# INF_Processing.net
KiCad netlist of a schematic drawn in Altium Designer
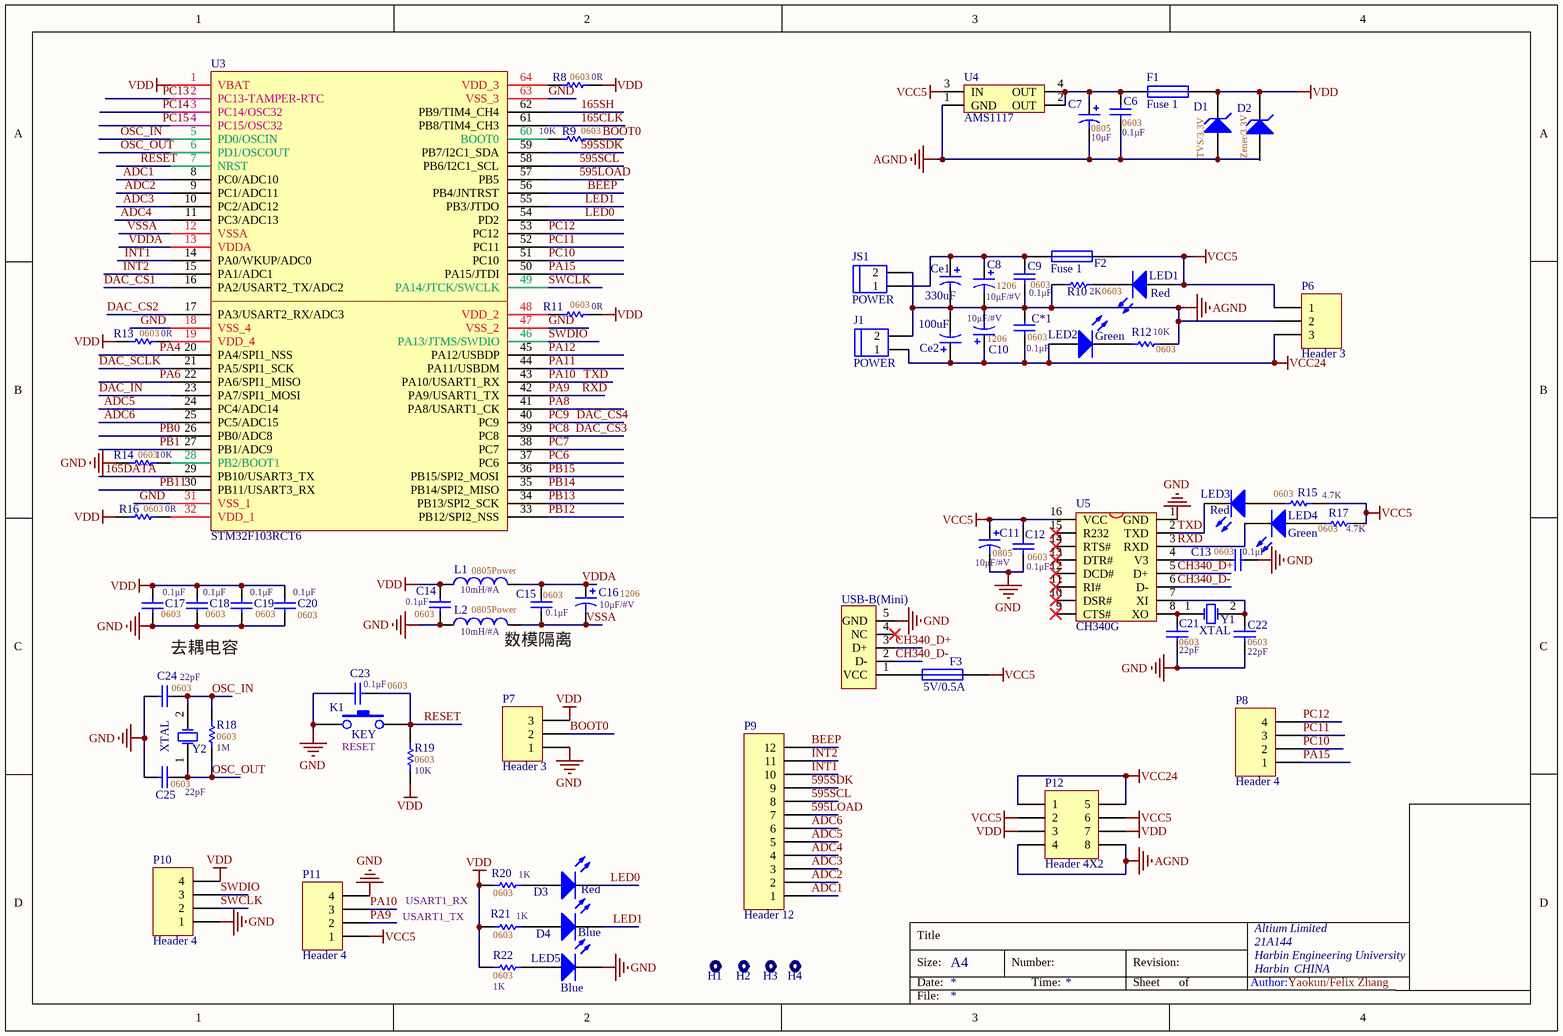
[diagram p0: INF_Processing.SchDoc]

(export (version "E")
  (design (tool "Eeschema 10.0.6"))
  (components
    (comp (ref "C*1")
      (value "0.1μF")
      (footprint "CAP_0603_16*08")
      (description "Capacitor")
      (fields
        (field (name "PACKAGEREFERENCE") "0603")
        (field (name "Comment") "0603")
        (field (name "PUBLISHER") "Altium Limited")
      )
      (libsource (lib "Belong_to_Kongkong") (part "Cap"))
    )
    (comp (ref "C6")
      (value "0.1μF")
      (footprint "CAP_0603_16*08")
      (description "Capacitor")
      (fields
        (field (name "PACKAGEREFERENCE") "0603")
        (field (name "Comment") "0603")
        (field (name "PUBLISHER") "Altium Limited")
      )
      (libsource (lib "Belong_to_Kongkong") (part "Cap"))
    )
    (comp (ref "C7")
      (value "10μF")
      (footprint "CAP_0805_20*12")
      (description "Polarized Capacitor (Axial)")
      (fields
        (field (name "PACKAGEREFERENCE") "0805")
        (field (name "Comment") "Polar")
        (field (name "PUBLISHER") "Altium Limited")
      )
      (libsource (lib "Belong_to_Kongkong") (part "Cap Pol"))
    )
    (comp (ref "C8")
      (value "10μF/#V")
      (footprint "CAP_1206")
      (description "Polarized Capacitor (Axial)")
      (fields
        (field (name "PACKAGEREFERENCE") "1206")
        (field (name "Comment") "Polar")
        (field (name "PUBLISHER") "Altium Limited")
      )
      (libsource (lib "Belong_to_Kongkong") (part "Cap Pol"))
    )
    (comp (ref "C9")
      (value "0.1μF")
      (footprint "CAP_0603_16*08")
      (description "Capacitor")
      (fields
        (field (name "PACKAGEREFERENCE") "0603")
        (field (name "Comment") "0603")
        (field (name "PUBLISHER") "Altium Limited")
      )
      (libsource (lib "Belong_to_Kongkong") (part "Cap"))
    )
    (comp (ref "C10")
      (value "10μF/#V")
      (footprint "CAP_1206")
      (description "Polarized Capacitor (Axial)")
      (fields
        (field (name "PACKAGEREFERENCE") "1206")
        (field (name "Comment") "Polar")
        (field (name "PUBLISHER") "Altium Limited")
      )
      (libsource (lib "Belong_to_Kongkong") (part "Cap Pol"))
    )
    (comp (ref "C11")
      (value "10μF/#V")
      (footprint "CAP_0805_20*12")
      (description "Polarized Capacitor (Axial)")
      (fields
        (field (name "PACKAGEREFERENCE") "0805")
        (field (name "Comment") "Polar")
        (field (name "PUBLISHER") "Altium Limited")
      )
      (libsource (lib "Belong_to_Kongkong") (part "Cap Pol"))
    )
    (comp (ref "C12")
      (value "0.1μF")
      (footprint "CAP_0603_16*08")
      (description "Capacitor")
      (fields
        (field (name "PACKAGEREFERENCE") "0603")
        (field (name "Comment") "0603")
        (field (name "PUBLISHER") "Altium Limited")
      )
      (libsource (lib "Belong_to_Kongkong") (part "Cap"))
    )
    (comp (ref "C13")
      (value "0.1μF")
      (footprint "CAP_0603_16*08")
      (description "Capacitor")
      (fields
        (field (name "PACKAGEREFERENCE") "0603")
        (field (name "Comment") "0603")
        (field (name "PUBLISHER") "Altium Limited")
      )
      (libsource (lib "Belong_to_Kongkong") (part "Cap"))
    )
    (comp (ref "C14")
      (value "0.1μF")
      (footprint "CAP_0603_16*08")
      (description "Capacitor")
      (fields
        (field (name "PACKAGEREFERENCE") "0603")
        (field (name "Comment") "0603")
        (field (name "PUBLISHER") "Altium Limited")
      )
      (libsource (lib "Belong_to_Kongkong") (part "Cap"))
    )
    (comp (ref "C15")
      (value "0.1μF")
      (footprint "CAP_0603_16*08")
      (description "Capacitor")
      (fields
        (field (name "PACKAGEREFERENCE") "0603")
        (field (name "Comment") "0603")
        (field (name "PUBLISHER") "Altium Limited")
      )
      (libsource (lib "Belong_to_Kongkong") (part "Cap"))
    )
    (comp (ref "C16")
      (value "10μF/#V")
      (footprint "CAP_0805_20*12")
      (description "Polarized Capacitor (Axial)")
      (fields
        (field (name "PACKAGEREFERENCE") "1206")
        (field (name "Comment") "Polar")
        (field (name "PUBLISHER") "Altium Limited")
      )
      (libsource (lib "Belong_to_Kongkong") (part "Cap Pol"))
    )
    (comp (ref "C17")
      (value "0.1μF")
      (footprint "CAP_0603_16*08")
      (description "Capacitor")
      (fields
        (field (name "PACKAGEREFERENCE") "0603")
        (field (name "Comment") "0603")
        (field (name "PUBLISHER") "Altium Limited")
      )
      (libsource (lib "Belong_to_Kongkong") (part "Cap"))
    )
    (comp (ref "C18")
      (value "0.1μF")
      (footprint "CAP_0603_16*08")
      (description "Capacitor")
      (fields
        (field (name "PACKAGEREFERENCE") "0603")
        (field (name "Comment") "0603")
        (field (name "PUBLISHER") "Altium Limited")
      )
      (libsource (lib "Belong_to_Kongkong") (part "Cap"))
    )
    (comp (ref "C19")
      (value "0.1μF")
      (footprint "CAP_0603_16*08")
      (description "Capacitor")
      (fields
        (field (name "PACKAGEREFERENCE") "0603")
        (field (name "Comment") "0603")
        (field (name "PUBLISHER") "Altium Limited")
      )
      (libsource (lib "Belong_to_Kongkong") (part "Cap"))
    )
    (comp (ref "C20")
      (value "0.1μF")
      (footprint "CAP_0603_16*08")
      (description "Capacitor")
      (fields
        (field (name "PACKAGEREFERENCE") "0603")
        (field (name "Comment") "0603")
        (field (name "PUBLISHER") "Altium Limited")
      )
      (libsource (lib "Belong_to_Kongkong") (part "Cap"))
    )
    (comp (ref "C21")
      (value "22pF")
      (footprint "CAP_0603_16*08")
      (description "Capacitor")
      (fields
        (field (name "PACKAGEREFERENCE") "0603")
        (field (name "Comment") "0603")
        (field (name "PUBLISHER") "Altium Limited")
      )
      (libsource (lib "Belong_to_Kongkong") (part "Cap"))
    )
    (comp (ref "C22")
      (value "22pF")
      (footprint "CAP_0603_16*08")
      (description "Capacitor")
      (fields
        (field (name "PACKAGEREFERENCE") "0603")
        (field (name "Comment") "0603")
        (field (name "PUBLISHER") "Altium Limited")
      )
      (libsource (lib "Belong_to_Kongkong") (part "Cap"))
    )
    (comp (ref "C23")
      (value "0.1μF")
      (footprint "CAP_0603_16*08")
      (description "Capacitor")
      (fields
        (field (name "PACKAGEREFERENCE") "0603")
        (field (name "Comment") "0603")
        (field (name "PUBLISHER") "Altium Limited")
      )
      (libsource (lib "Belong_to_Kongkong") (part "Cap"))
    )
    (comp (ref "C24")
      (value "22pF")
      (footprint "CAP_0603_16*08")
      (description "Capacitor")
      (fields
        (field (name "PACKAGEREFERENCE") "0603")
        (field (name "Comment") "0603")
        (field (name "PUBLISHER") "Altium Limited")
      )
      (libsource (lib "Belong_to_Kongkong") (part "Cap"))
    )
    (comp (ref "C25")
      (value "22pF")
      (footprint "CAP_0603_16*08")
      (description "Capacitor")
      (fields
        (field (name "PACKAGEREFERENCE") "0603")
        (field (name "Comment") "0603")
        (field (name "PUBLISHER") "Altium Limited")
      )
      (libsource (lib "Belong_to_Kongkong") (part "Cap"))
    )
    (comp (ref "Ce1")
      (value "330uF")
      (footprint "Cap_elc_330uF16V")
      (libsource (lib "Belong_to_Kongkong") (part "Cap Elec"))
    )
    (comp (ref "Ce2")
      (value "100uF")
      (footprint "Cap_elc_100uF35V")
      (libsource (lib "Belong_to_Kongkong") (part "Cap Elec"))
    )
    (comp (ref "D1")
      (value "TVS/3.3V")
      (footprint "SOD523")
      (description "Zener Diode")
      (fields (field (name "PUBLISHER") "Altium Limited"))
      (libsource (lib "Belong_to_Kongkong") (part "D Zener"))
    )
    (comp (ref "D2")
      (value "Zener/3.3V")
      (footprint "SOD323")
      (description "Zener Diode")
      (fields (field (name "PUBLISHER") "Altium Limited"))
      (libsource (lib "Belong_to_Kongkong") (part "D Zener"))
    )
    (comp (ref "D3")
      (value "Red")
      (footprint "LED_0805")
      (description "Typical RED, GREEN, YELLOW, AMBER GaAs LED")
      (fields (field (name "PUBLISHER") "Altium Limited"))
      (libsource (lib "Belong_to_Kongkong") (part "LED"))
    )
    (comp (ref "D4")
      (value "Blue")
      (footprint "LED_0805")
      (description "Typical RED, GREEN, YELLOW, AMBER GaAs LED")
      (fields (field (name "PUBLISHER") "Altium Limited"))
      (libsource (lib "Belong_to_Kongkong") (part "LED"))
    )
    (comp (ref "F1")
      (value "Fuse 1")
      (footprint "RES_0805_20*12")
      (description "Fuse")
      (fields (field (name "PUBLISHER") "Altium Limited"))
      (libsource (lib "Belong_to_Kongkong") (part "Fuse 1"))
    )
    (comp (ref "F2")
      (value "Fuse 1")
      (footprint "FUSE3.5*5.5")
      (description "Fuse")
      (fields (field (name "PUBLISHER") "Altium Limited"))
      (libsource (lib "Belong_to_Kongkong") (part "Fuse 1"))
    )
    (comp (ref "F3")
      (value "5V/0.5A")
      (footprint "RES_0805_20*12")
      (description "Fuse")
      (fields (field (name "PUBLISHER") "Altium Limited"))
      (libsource (lib "Belong_to_Kongkong") (part "Fuse 1"))
    )
    (comp (ref "H1")
      (value "Pad3mm")
      (footprint "PAD")
      (libsource (lib "Belong_to_Kongkong") (part "Pad3mm"))
    )
    (comp (ref "H2")
      (value "Pad3mm")
      (footprint "PAD")
      (libsource (lib "Belong_to_Kongkong") (part "Pad3mm"))
    )
    (comp (ref "H3")
      (value "Pad3mm")
      (footprint "PAD")
      (libsource (lib "Belong_to_Kongkong") (part "Pad3mm"))
    )
    (comp (ref "H4")
      (value "Pad3mm")
      (footprint "PAD")
      (libsource (lib "Belong_to_Kongkong") (part "Pad3mm"))
    )
    (comp (ref "J1")
      (value "POWER")
      (footprint "Header2_press")
      (libsource (lib "Belong_to_Kongkong") (part "HEAD2"))
    )
    (comp (ref "JS1")
      (value "POWER")
      (footprint "Header2_press")
      (libsource (lib "Belong_to_Kongkong") (part "HEAD2"))
    )
    (comp (ref "K1")
      (value "KEY")
      (footprint "KEY_4")
      (fields (field (name "ALTIUM_UNNAMED_1") "RESET"))
      (libsource (lib "Belong_to_Kongkong") (part "KEY"))
    )
    (comp (ref "L1")
      (value "10mH/#A")
      (footprint "IND_0805_20*12")
      (description "Inductor")
      (fields
        (field (name "PACKAGEREFERENCE") "0805")
        (field (name "PACKAGEDESCRIPTION") "Power")
        (field (name "Comment") "MODEL?")
        (field (name "PUBLISHER") "Altium Limited")
      )
      (libsource (lib "Belong_to_Kongkong") (part "Inductor"))
    )
    (comp (ref "L2")
      (value "10mH/#A")
      (footprint "IND_0805_20*12")
      (description "Inductor")
      (fields
        (field (name "PACKAGEREFERENCE") "0805")
        (field (name "PACKAGEDESCRIPTION") "Power")
        (field (name "Comment") "MODEL?")
        (field (name "PUBLISHER") "Altium Limited")
      )
      (libsource (lib "Belong_to_Kongkong") (part "Inductor"))
    )
    (comp (ref "LED1")
      (value "Red")
      (footprint "LED_0805")
      (description "Typical RED, GREEN, YELLOW, AMBER GaAs LED")
      (fields (field (name "PUBLISHER") "Altium Limited"))
      (libsource (lib "Belong_to_Kongkong") (part "LED"))
    )
    (comp (ref "LED2")
      (value "Green")
      (footprint "LED_0805")
      (description "Typical RED, GREEN, YELLOW, AMBER GaAs LED")
      (fields (field (name "PUBLISHER") "Altium Limited"))
      (libsource (lib "Belong_to_Kongkong") (part "LED"))
    )
    (comp (ref "LED3")
      (value "Red")
      (footprint "CAP_0603_16*08")
      (description "Typical RED, GREEN, YELLOW, AMBER GaAs LED")
      (fields (field (name "PUBLISHER") "Altium Limited"))
      (libsource (lib "Belong_to_Kongkong") (part "LED"))
    )
    (comp (ref "LED4")
      (value "Green")
      (footprint "CAP_0603_16*08")
      (description "Typical RED, GREEN, YELLOW, AMBER GaAs LED")
      (fields (field (name "PUBLISHER") "Altium Limited"))
      (libsource (lib "Belong_to_Kongkong") (part "LED"))
    )
    (comp (ref "LED5")
      (value "Blue")
      (footprint "LED_0805")
      (description "Typical RED, GREEN, YELLOW, AMBER GaAs LED")
      (fields (field (name "PUBLISHER") "Altium Limited"))
      (libsource (lib "Belong_to_Kongkong") (part "LED"))
    )
    (comp (ref "P6")
      (value "Header 3")
      (footprint "Header3_HC5.08")
      (description "Header, 3-Pin")
      (fields (field (name "PUBLISHER") "Altium Limited"))
      (libsource (lib "Belong_to_Kongkong") (part "Header 3"))
    )
    (comp (ref "P7")
      (value "Header 3")
      (footprint "HEADER1*3_PIN")
      (description "Header, 3-Pin")
      (fields (field (name "PUBLISHER") "Altium Limited"))
      (libsource (lib "") (part "Header 3_1"))
    )
    (comp (ref "P8")
      (value "Header 4")
      (footprint "HEADER1*4_PIN")
      (description "Header, 4-Pin")
      (fields (field (name "PUBLISHER") "Altium Limited"))
      (libsource (lib "Belong_to_Kongkong") (part "Header 4"))
    )
    (comp (ref "P9")
      (value "Header 12")
      (footprint "P12_OUT")
      (description "Header, 12-Pin")
      (fields (field (name "PUBLISHER") "Altium Limited"))
      (libsource (lib "Belong_to_Kongkong") (part "Header 12"))
    )
    (comp (ref "P10")
      (value "Header 4")
      (footprint "P4_OUT")
      (description "Header, 4-Pin")
      (fields (field (name "PUBLISHER") "Altium Limited"))
      (libsource (lib "Belong_to_Kongkong") (part "Header 4"))
    )
    (comp (ref "P11")
      (value "Header 4")
      (footprint "HEADER1*4_PIN")
      (description "Header, 4-Pin")
      (fields (field (name "PUBLISHER") "Altium Limited"))
      (libsource (lib "Belong_to_Kongkong") (part "Header 4"))
    )
    (comp (ref "P12")
      (value "Header 4X2")
      (footprint "HEADER2*4_PIN")
      (description "Header, 4-Pin, Dual row")
      (fields (field (name "PUBLISHER") "Altium Limited"))
      (libsource (lib "Belong_to_Kongkong") (part "Header 4X2"))
    )
    (comp (ref "R8")
      (value "0R")
      (footprint "RES_0603_16*08")
      (description "Resistor")
      (fields
        (field (name "PACKAGEREFERENCE") "0603")
        (field (name "Comment") "SMD")
        (field (name "PUBLISHER") "Altium Limited")
      )
      (libsource (lib "Belong_to_Kongkong") (part "RES_SMD"))
    )
    (comp (ref "R9")
      (value "10K")
      (footprint "RES_0603_16*08")
      (description "Resistor")
      (fields
        (field (name "PACKAGEREFERENCE") "0603")
        (field (name "Comment") "SMD")
        (field (name "PUBLISHER") "Altium Limited")
      )
      (libsource (lib "Belong_to_Kongkong") (part "RES_SMD"))
    )
    (comp (ref "R10")
      (value "2K")
      (footprint "RES_0805_20*12")
      (description "Resistor")
      (fields
        (field (name "PACKAGEREFERENCE") "0603")
        (field (name "Comment") "SMD")
        (field (name "PUBLISHER") "Altium Limited")
      )
      (libsource (lib "Belong_to_Kongkong") (part "RES_SMD"))
    )
    (comp (ref "R11")
      (value "0R")
      (footprint "RES_0603_16*08")
      (description "Resistor")
      (fields
        (field (name "PACKAGEREFERENCE") "0603")
        (field (name "Comment") "SMD")
        (field (name "PUBLISHER") "Altium Limited")
      )
      (libsource (lib "Belong_to_Kongkong") (part "RES_SMD"))
    )
    (comp (ref "R12")
      (value "10K")
      (footprint "RES_0805_20*12")
      (description "Resistor")
      (fields
        (field (name "PACKAGEREFERENCE") "0603")
        (field (name "Comment") "SMD")
        (field (name "PUBLISHER") "Altium Limited")
      )
      (libsource (lib "Belong_to_Kongkong") (part "RES_SMD"))
    )
    (comp (ref "R13")
      (value "0R")
      (footprint "RES_0603_16*08")
      (description "Resistor")
      (fields
        (field (name "PACKAGEREFERENCE") "0603")
        (field (name "Comment") "SMD")
        (field (name "PUBLISHER") "Altium Limited")
      )
      (libsource (lib "Belong_to_Kongkong") (part "RES_SMD"))
    )
    (comp (ref "R14")
      (value "10K")
      (footprint "RES_0603_16*08")
      (description "Resistor")
      (fields
        (field (name "PACKAGEREFERENCE") "0603")
        (field (name "Comment") "SMD")
        (field (name "PUBLISHER") "Altium Limited")
      )
      (libsource (lib "Belong_to_Kongkong") (part "RES_SMD"))
    )
    (comp (ref "R15")
      (value "4.7K")
      (footprint "RES_0603_16*08")
      (description "Resistor")
      (fields
        (field (name "PACKAGEREFERENCE") "0603")
        (field (name "Comment") "SMD")
        (field (name "PUBLISHER") "Altium Limited")
      )
      (libsource (lib "Belong_to_Kongkong") (part "RES_SMD"))
    )
    (comp (ref "R16")
      (value "0R")
      (footprint "RES_0603_16*08")
      (description "Resistor")
      (fields
        (field (name "PACKAGEREFERENCE") "0603")
        (field (name "Comment") "SMD")
        (field (name "PUBLISHER") "Altium Limited")
      )
      (libsource (lib "Belong_to_Kongkong") (part "RES_SMD"))
    )
    (comp (ref "R17")
      (value "4.7K")
      (footprint "RES_0603_16*08")
      (description "Resistor")
      (fields
        (field (name "PACKAGEREFERENCE") "0603")
        (field (name "Comment") "SMD")
        (field (name "PUBLISHER") "Altium Limited")
      )
      (libsource (lib "Belong_to_Kongkong") (part "RES_SMD"))
    )
    (comp (ref "R18")
      (value "1M")
      (footprint "RES_0805_20*12")
      (description "Resistor")
      (fields
        (field (name "PACKAGEREFERENCE") "0603")
        (field (name "Comment") "SMD")
        (field (name "PUBLISHER") "Altium Limited")
      )
      (libsource (lib "Belong_to_Kongkong") (part "RES_SMD"))
    )
    (comp (ref "R19")
      (value "10K")
      (footprint "RES_0603_16*08")
      (description "Resistor")
      (fields
        (field (name "PACKAGEREFERENCE") "0603")
        (field (name "Comment") "SMD")
        (field (name "PUBLISHER") "Altium Limited")
      )
      (libsource (lib "Belong_to_Kongkong") (part "RES_SMD"))
    )
    (comp (ref "R20")
      (value "1K")
      (footprint "RES_0805_20*12")
      (description "Resistor")
      (fields
        (field (name "PACKAGEREFERENCE") "0603")
        (field (name "Comment") "SMD")
        (field (name "PUBLISHER") "Altium Limited")
      )
      (libsource (lib "Belong_to_Kongkong") (part "RES_SMD"))
    )
    (comp (ref "R21")
      (value "1K")
      (footprint "RES_0805_20*12")
      (description "Resistor")
      (fields
        (field (name "PACKAGEREFERENCE") "0603")
        (field (name "Comment") "SMD")
        (field (name "PUBLISHER") "Altium Limited")
      )
      (libsource (lib "Belong_to_Kongkong") (part "RES_SMD"))
    )
    (comp (ref "R22")
      (value "1K")
      (footprint "RES_0805_20*12")
      (description "Resistor")
      (fields
        (field (name "PACKAGEREFERENCE") "0603")
        (field (name "Comment") "SMD")
        (field (name "PUBLISHER") "Altium Limited")
      )
      (libsource (lib "Belong_to_Kongkong") (part "RES_SMD"))
    )
    (comp (ref "U3")
      (value "STM32F103RCT6")
      (footprint "LQFP64_N")
      (libsource (lib "Belong_to_Kongkong") (part "STM32F103RBT6"))
    )
    (comp (ref "U4")
      (value "AMS1117")
      (footprint "SOT223_M")
      (libsource (lib "Belong_to_Kongkong") (part "AMS1117"))
    )
    (comp (ref "U5")
      (value "CH340G")
      (footprint "SOP16")
      (description "USB2UART")
      (libsource (lib "Belong_to_Kongkong") (part "CH340G"))
    )
    (comp (ref "USB_SLAVE1")
      (value "USB-B(Mini)")
      (footprint "USB/SM0.8-6H5")
      (libsource (lib "Belong_to_Kongkong") (part "USB5"))
    )
    (comp (ref "Y1")
      (value "XTAL")
      (footprint "XTAL_US")
      (description "Crystal Oscillator")
      (fields (field (name "PUBLISHER") "Altium Limited"))
      (libsource (lib "Belong_to_Kongkong") (part "XTAL"))
    )
    (comp (ref "Y2")
      (value "XTAL")
      (footprint "XTAL_US")
      (description "Crystal Oscillator")
      (fields (field (name "PUBLISHER") "Altium Limited"))
      (libsource (lib "Belong_to_Kongkong") (part "XTAL"))
    )
  )
  (nets
    (net (code "1") (name "/165CLK") (class "Default")
      (node (ref "U3") (pin "61") (pinfunction "PB8/TIM4_CH3_61") (pintype "passive"))
    )
    (net (code "2") (name "/165DATA") (class "Default")
      (node (ref "U3") (pin "29") (pinfunction "PB10/USART3_TX_29") (pintype "passive"))
    )
    (net (code "3") (name "/165SH") (class "Default")
      (node (ref "U3") (pin "62") (pinfunction "PB9/TIM4_CH4_62") (pintype "passive"))
    )
    (net (code "4") (name "/595LOAD") (class "Default")
      (node (ref "P9") (pin "7") (pinfunction "7_7") (pintype "passive"))
      (node (ref "U3") (pin "57") (pinfunction "PB5_57") (pintype "passive"))
    )
    (net (code "5") (name "/595SCL") (class "Default")
      (node (ref "P9") (pin "8") (pinfunction "8_8") (pintype "passive"))
      (node (ref "U3") (pin "58") (pinfunction "PB6/I2C1_SCL_58") (pintype "passive"))
    )
    (net (code "6") (name "/595SDK") (class "Default")
      (node (ref "P9") (pin "9") (pinfunction "9_9") (pintype "passive"))
      (node (ref "U3") (pin "59") (pinfunction "PB7/I2C1_SDA_59") (pintype "passive"))
    )
    (net (code "7") (name "/ADC1") (class "Default")
      (node (ref "P9") (pin "1") (pinfunction "1_1") (pintype "passive"))
      (node (ref "U3") (pin "8") (pinfunction "PC0/ADC10_8") (pintype "passive"))
    )
    (net (code "8") (name "/ADC2") (class "Default")
      (node (ref "P9") (pin "2") (pinfunction "2_2") (pintype "passive"))
      (node (ref "U3") (pin "9") (pinfunction "PC1/ADC11_9") (pintype "passive"))
    )
    (net (code "9") (name "/ADC3") (class "Default")
      (node (ref "P9") (pin "3") (pinfunction "3_3") (pintype "passive"))
      (node (ref "U3") (pin "10") (pinfunction "PC2/ADC12_10") (pintype "passive"))
    )
    (net (code "10") (name "/ADC4") (class "Default")
      (node (ref "P9") (pin "4") (pinfunction "4_4") (pintype "passive"))
      (node (ref "U3") (pin "11") (pinfunction "PC3/ADC13_11") (pintype "passive"))
    )
    (net (code "11") (name "/ADC5") (class "Default")
      (node (ref "P9") (pin "5") (pinfunction "5_5") (pintype "passive"))
      (node (ref "U3") (pin "24") (pinfunction "PC4/ADC14_24") (pintype "passive"))
    )
    (net (code "12") (name "/ADC6") (class "Default")
      (node (ref "P9") (pin "6") (pinfunction "6_6") (pintype "passive"))
      (node (ref "U3") (pin "25") (pinfunction "PC5/ADC15_25") (pintype "passive"))
    )
    (net (code "13") (name "/BEEP") (class "Default")
      (node (ref "P9") (pin "12") (pinfunction "12_12") (pintype "passive"))
      (node (ref "U3") (pin "56") (pinfunction "PB4/JNTRST_56") (pintype "passive"))
    )
    (net (code "14") (name "/BOOT0") (class "Default")
      (node (ref "P7") (pin "2") (pinfunction "2_2") (pintype "passive"))
      (node (ref "R9") (pin "1") (pinfunction "1_1") (pintype "passive"))
    )
    (net (code "15") (name "/CH340_D+") (class "Default")
      (node (ref "U5") (pin "5") (pinfunction "D+_5") (pintype "passive"))
      (node (ref "USB_SLAVE1") (pin "3") (pinfunction "D+_3") (pintype "passive"))
    )
    (net (code "16") (name "/CH340_D-") (class "Default")
      (node (ref "U5") (pin "6") (pinfunction "D-_6") (pintype "passive"))
      (node (ref "USB_SLAVE1") (pin "2") (pinfunction "D-_2") (pintype "passive"))
    )
    (net (code "17") (name "/DAC_CS1") (class "Default")
      (node (ref "U3") (pin "16") (pinfunction "PA2/USART2_TX/ADC2_16") (pintype "passive"))
    )
    (net (code "18") (name "/DAC_CS2") (class "Default")
      (node (ref "U3") (pin "17") (pinfunction "PA3/USART2_RX/ADC3_17") (pintype "passive"))
    )
    (net (code "19") (name "/DAC_CS3") (class "Default")
      (node (ref "U3") (pin "39") (pinfunction "PC8_39") (pintype "passive"))
    )
    (net (code "20") (name "/DAC_CS4") (class "Default")
      (node (ref "U3") (pin "40") (pinfunction "PC9_40") (pintype "passive"))
    )
    (net (code "21") (name "/DAC_IN") (class "Default")
      (node (ref "U3") (pin "23") (pinfunction "PA7/SPI1_MOSI_23") (pintype "passive"))
    )
    (net (code "22") (name "/DAC_SCLK") (class "Default")
      (node (ref "U3") (pin "21") (pinfunction "PA5/SPI1_SCK_21") (pintype "passive"))
    )
    (net (code "23") (name "/INT1") (class "Default")
      (node (ref "P9") (pin "10") (pinfunction "10_10") (pintype "passive"))
      (node (ref "U3") (pin "14") (pinfunction "PA0/WKUP/ADC0_14") (pintype "passive"))
    )
    (net (code "24") (name "/INT2") (class "Default")
      (node (ref "P9") (pin "11") (pinfunction "11_11") (pintype "passive"))
      (node (ref "U3") (pin "15") (pinfunction "PA1/ADC1_15") (pintype "passive"))
    )
    (net (code "25") (name "/LED0") (class "Default")
      (node (ref "D3") (pin "2") (pinfunction "K_2") (pintype "passive"))
      (node (ref "U3") (pin "54") (pinfunction "PD2_54") (pintype "passive"))
    )
    (net (code "26") (name "/LED1") (class "Default")
      (node (ref "D4") (pin "2") (pinfunction "K_2") (pintype "passive"))
      (node (ref "U3") (pin "55") (pinfunction "PB3/JTDO_55") (pintype "passive"))
    )
    (net (code "27") (name "/OSC_IN") (class "Default")
      (node (ref "C24") (pin "1") (pinfunction "1_1") (pintype "passive"))
      (node (ref "R18") (pin "2") (pinfunction "2_2") (pintype "passive"))
      (node (ref "U3") (pin "5") (pinfunction "PD0/OSCIN_5") (pintype "passive"))
      (node (ref "Y2") (pin "2") (pinfunction "OSC2_2") (pintype "passive"))
    )
    (net (code "28") (name "/OSC_OUT") (class "Default")
      (node (ref "C25") (pin "1") (pinfunction "1_1") (pintype "passive"))
      (node (ref "R18") (pin "1") (pinfunction "1_1") (pintype "passive"))
      (node (ref "U3") (pin "6") (pinfunction "PD1/OSCOUT_6") (pintype "passive"))
      (node (ref "Y2") (pin "1") (pinfunction "OSC1_1") (pintype "passive"))
    )
    (net (code "29") (name "/PA4") (class "Default")
      (node (ref "U3") (pin "20") (pinfunction "PA4/SPI1_NSS_20") (pintype "passive"))
    )
    (net (code "30") (name "/PA6") (class "Default")
      (node (ref "U3") (pin "22") (pinfunction "PA6/SPI1_MISO_22") (pintype "passive"))
    )
    (net (code "31") (name "/PA8") (class "Default")
      (node (ref "U3") (pin "41") (pinfunction "PA8/USART1_CK_41") (pintype "passive"))
    )
    (net (code "32") (name "/PA9") (class "Default")
      (node (ref "LED4") (pin "2") (pinfunction "K_2") (pintype "passive"))
      (node (ref "P11") (pin "2") (pinfunction "2_2") (pintype "passive"))
      (node (ref "U3") (pin "42") (pinfunction "PA9/USART1_TX_42") (pintype "passive"))
      (node (ref "U5") (pin "3") (pinfunction "RXD_3") (pintype "passive"))
    )
    (net (code "33") (name "/PA10") (class "Default")
      (node (ref "LED3") (pin "2") (pinfunction "K_2") (pintype "passive"))
      (node (ref "P11") (pin "3") (pinfunction "3_3") (pintype "passive"))
      (node (ref "U3") (pin "43") (pinfunction "PA10/USART1_RX_43") (pintype "passive"))
      (node (ref "U5") (pin "2") (pinfunction "TXD_2") (pintype "passive"))
    )
    (net (code "34") (name "/PA11") (class "Default")
      (node (ref "U3") (pin "44") (pinfunction "PA11/USBDM_44") (pintype "passive"))
    )
    (net (code "35") (name "/PA12") (class "Default")
      (node (ref "U3") (pin "45") (pinfunction "PA12/USBDP_45") (pintype "passive"))
    )
    (net (code "36") (name "/PA15") (class "Default")
      (node (ref "P8") (pin "1") (pinfunction "1_1") (pintype "passive"))
      (node (ref "U3") (pin "50") (pinfunction "PA15/JTDI_50") (pintype "passive"))
    )
    (net (code "37") (name "/PB0") (class "Default")
      (node (ref "U3") (pin "26") (pinfunction "PB0/ADC8_26") (pintype "passive"))
    )
    (net (code "38") (name "/PB1") (class "Default")
      (node (ref "U3") (pin "27") (pinfunction "PB1/ADC9_27") (pintype "passive"))
    )
    (net (code "39") (name "/PB11") (class "Default")
      (node (ref "U3") (pin "30") (pinfunction "PB11/USART3_RX_30") (pintype "passive"))
    )
    (net (code "40") (name "/PB12") (class "Default")
      (node (ref "U3") (pin "33") (pinfunction "PB12/SPI2_NSS_33") (pintype "passive"))
    )
    (net (code "41") (name "/PB13") (class "Default")
      (node (ref "U3") (pin "34") (pinfunction "PB13/SPI2_SCK_34") (pintype "passive"))
    )
    (net (code "42") (name "/PB14") (class "Default")
      (node (ref "U3") (pin "35") (pinfunction "PB14/SPI2_MISO_35") (pintype "passive"))
    )
    (net (code "43") (name "/PB15") (class "Default")
      (node (ref "U3") (pin "36") (pinfunction "PB15/SPI2_MOSI_36") (pintype "passive"))
    )
    (net (code "44") (name "/PC6") (class "Default")
      (node (ref "U3") (pin "37") (pinfunction "PC6_37") (pintype "passive"))
    )
    (net (code "45") (name "/PC7") (class "Default")
      (node (ref "U3") (pin "38") (pinfunction "PC7_38") (pintype "passive"))
    )
    (net (code "46") (name "/PC10") (class "Default")
      (node (ref "P8") (pin "2") (pinfunction "2_2") (pintype "passive"))
      (node (ref "U3") (pin "51") (pinfunction "PC10_51") (pintype "passive"))
    )
    (net (code "47") (name "/PC11") (class "Default")
      (node (ref "P8") (pin "3") (pinfunction "3_3") (pintype "passive"))
      (node (ref "U3") (pin "52") (pinfunction "PC11_52") (pintype "passive"))
    )
    (net (code "48") (name "/PC12") (class "Default")
      (node (ref "P8") (pin "4") (pinfunction "4_4") (pintype "passive"))
      (node (ref "U3") (pin "53") (pinfunction "PC12_53") (pintype "passive"))
    )
    (net (code "49") (name "/PC13") (class "Default")
      (node (ref "U3") (pin "2") (pinfunction "PC13-TAMPER-RTC_2") (pintype "passive"))
    )
    (net (code "50") (name "/PC14") (class "Default")
      (node (ref "U3") (pin "3") (pinfunction "PC14/OSC32_3") (pintype "passive"))
    )
    (net (code "51") (name "/PC15") (class "Default")
      (node (ref "U3") (pin "4") (pinfunction "PC15/OSC32_4") (pintype "passive"))
    )
    (net (code "52") (name "/RESET") (class "Default")
      (node (ref "C23") (pin "2") (pinfunction "2_2") (pintype "passive"))
      (node (ref "K1") (pin "2") (pinfunction "2_2") (pintype "passive"))
      (node (ref "R19") (pin "2") (pinfunction "2_2") (pintype "passive"))
      (node (ref "U3") (pin "7") (pinfunction "NRST_7") (pintype "passive"))
    )
    (net (code "53") (name "/SWCLK") (class "Default")
      (node (ref "P10") (pin "2") (pinfunction "2_2") (pintype "passive"))
      (node (ref "U3") (pin "49") (pinfunction "PA14/JTCK/SWCLK_49") (pintype "passive"))
    )
    (net (code "54") (name "/SWDIO") (class "Default")
      (node (ref "P10") (pin "3") (pinfunction "3_3") (pintype "passive"))
      (node (ref "U3") (pin "46") (pinfunction "PA13/JTMS/SWDIO_46") (pintype "passive"))
    )
    (net (code "55") (name "/VDDA") (class "Default")
      (node (ref "C15") (pin "2") (pinfunction "2_2") (pintype "passive"))
      (node (ref "C16") (pin "1") (pinfunction "1_1") (pintype "passive"))
      (node (ref "L1") (pin "2") (pinfunction "2_2") (pintype "passive"))
      (node (ref "U3") (pin "13") (pinfunction "VDDA_13") (pintype "passive"))
    )
    (net (code "56") (name "/VSSA") (class "Default")
      (node (ref "C15") (pin "1") (pinfunction "1_1") (pintype "passive"))
      (node (ref "C16") (pin "2") (pinfunction "2_2") (pintype "passive"))
      (node (ref "L2") (pin "2") (pinfunction "2_2") (pintype "passive"))
      (node (ref "U3") (pin "12") (pinfunction "VSSA_12") (pintype "passive"))
    )
    (net (code "57") (name "AGND") (class "Default")
      (node (ref "C*1") (pin "2") (pinfunction "2_2") (pintype "passive"))
      (node (ref "C10") (pin "2") (pinfunction "2_2") (pintype "passive"))
      (node (ref "C6") (pin "1") (pinfunction "1_1") (pintype "passive"))
      (node (ref "C7") (pin "2") (pinfunction "2_2") (pintype "passive"))
      (node (ref "C8") (pin "2") (pinfunction "2_2") (pintype "passive"))
      (node (ref "C9") (pin "1") (pinfunction "1_1") (pintype "passive"))
      (node (ref "Ce1") (pin "2") (pinfunction "2_2") (pintype "passive"))
      (node (ref "Ce2") (pin "2") (pinfunction "2_2") (pintype "passive"))
      (node (ref "D1") (pin "1") (pinfunction "A_1") (pintype "passive"))
      (node (ref "D2") (pin "1") (pinfunction "A_1") (pintype "passive"))
      (node (ref "J1") (pin "2") (pinfunction "2_2") (pintype "passive"))
      (node (ref "JS1") (pin "2") (pinfunction "2_2") (pintype "passive"))
      (node (ref "P12") (pin "4") (pinfunction "4_4") (pintype "passive"))
      (node (ref "P12") (pin "8") (pinfunction "8_8") (pintype "passive"))
      (node (ref "P6") (pin "2") (pinfunction "2_2") (pintype "passive"))
      (node (ref "R10") (pin "1") (pinfunction "1_1") (pintype "passive"))
      (node (ref "R12") (pin "2") (pinfunction "2_2") (pintype "passive"))
      (node (ref "U4") (pin "1") (pinfunction "GND_1") (pintype "passive"))
    )
    (net (code "58") (name "GND") (class "Default")
      (node (ref "C11") (pin "2") (pinfunction "2_2") (pintype "passive"))
      (node (ref "C12") (pin "1") (pinfunction "1_1") (pintype "passive"))
      (node (ref "C13") (pin "2") (pinfunction "2_2") (pintype "passive"))
      (node (ref "C14") (pin "1") (pinfunction "1_1") (pintype "passive"))
      (node (ref "C17") (pin "2") (pinfunction "2_2") (pintype "passive"))
      (node (ref "C18") (pin "2") (pinfunction "2_2") (pintype "passive"))
      (node (ref "C19") (pin "2") (pinfunction "2_2") (pintype "passive"))
      (node (ref "C20") (pin "1") (pinfunction "1_1") (pintype "passive"))
      (node (ref "C21") (pin "1") (pinfunction "1_1") (pintype "passive"))
      (node (ref "C22") (pin "1") (pinfunction "1_1") (pintype "passive"))
      (node (ref "C23") (pin "1") (pinfunction "1_1") (pintype "passive"))
      (node (ref "C24") (pin "2") (pinfunction "2_2") (pintype "passive"))
      (node (ref "C25") (pin "2") (pinfunction "2_2") (pintype "passive"))
      (node (ref "K1") (pin "1") (pinfunction "1_1") (pintype "passive"))
      (node (ref "L2") (pin "1") (pinfunction "1_1") (pintype "passive"))
      (node (ref "LED5") (pin "2") (pinfunction "K_2") (pintype "passive"))
      (node (ref "P10") (pin "1") (pinfunction "1_1") (pintype "passive"))
      (node (ref "P11") (pin "4") (pinfunction "4_4") (pintype "passive"))
      (node (ref "P7") (pin "1") (pinfunction "1_1") (pintype "passive"))
      (node (ref "R14") (pin "1") (pinfunction "1_1") (pintype "passive"))
      (node (ref "U3") (pin "18") (pinfunction "VSS_4_18") (pintype "passive"))
      (node (ref "U3") (pin "31") (pinfunction "VSS_1_31") (pintype "passive"))
      (node (ref "U3") (pin "47") (pinfunction "VSS_2_47") (pintype "passive"))
      (node (ref "U3") (pin "63") (pinfunction "VSS_3_63") (pintype "passive"))
      (node (ref "U5") (pin "1") (pinfunction "GND_1") (pintype "passive"))
      (node (ref "USB_SLAVE1") (pin "5") (pinfunction "GND_5") (pintype "passive"))
    )
    (net (code "59") (name "Net-(C6-Pad2)") (class "Default")
      (node (ref "C6") (pin "2") (pinfunction "2_2") (pintype "passive"))
      (node (ref "C7") (pin "1") (pinfunction "1_1") (pintype "passive"))
      (node (ref "F1") (pin "1") (pinfunction "1_1") (pintype "passive"))
      (node (ref "U4") (pin "2") (pinfunction "OUT_2") (pintype "passive"))
      (node (ref "U4") (pin "4") (pinfunction "OUT_4") (pintype "passive"))
    )
    (net (code "60") (name "Net-(Ce1-+)") (class "Default")
      (node (ref "C8") (pin "1") (pinfunction "1_1") (pintype "passive"))
      (node (ref "C9") (pin "2") (pinfunction "2_2") (pintype "passive"))
      (node (ref "Ce1") (pin "1") (pinfunction "+_1") (pintype "passive"))
      (node (ref "F2") (pin "1") (pinfunction "1_1") (pintype "passive"))
      (node (ref "JS1") (pin "1") (pinfunction "1_1") (pintype "passive"))
    )
    (net (code "61") (name "Net-(D3-A)") (class "Default")
      (node (ref "D3") (pin "1") (pinfunction "A_1") (pintype "passive"))
      (node (ref "R20") (pin "2") (pinfunction "2_2") (pintype "passive"))
    )
    (net (code "62") (name "Net-(D4-A)") (class "Default")
      (node (ref "D4") (pin "1") (pinfunction "A_1") (pintype "passive"))
      (node (ref "R21") (pin "2") (pinfunction "2_2") (pintype "passive"))
    )
    (net (code "63") (name "Net-(LED1-K)") (class "Default")
      (node (ref "LED1") (pin "2") (pinfunction "K_2") (pintype "passive"))
      (node (ref "R10") (pin "2") (pinfunction "2_2") (pintype "passive"))
    )
    (net (code "64") (name "Net-(LED2-K)") (class "Default")
      (node (ref "LED2") (pin "2") (pinfunction "K_2") (pintype "passive"))
      (node (ref "R12") (pin "1") (pinfunction "1_1") (pintype "passive"))
    )
    (net (code "65") (name "Net-(LED3-A)") (class "Default")
      (node (ref "LED3") (pin "1") (pinfunction "A_1") (pintype "passive"))
      (node (ref "R15") (pin "1") (pinfunction "1_1") (pintype "passive"))
    )
    (net (code "66") (name "Net-(LED4-A)") (class "Default")
      (node (ref "LED4") (pin "1") (pinfunction "A_1") (pintype "passive"))
      (node (ref "R17") (pin "2") (pinfunction "2_2") (pintype "passive"))
    )
    (net (code "67") (name "Net-(LED5-A)") (class "Default")
      (node (ref "LED5") (pin "1") (pinfunction "A_1") (pintype "passive"))
      (node (ref "R22") (pin "1") (pinfunction "1_1") (pintype "passive"))
    )
    (net (code "68") (name "Net-(U3-BOOT0)") (class "Default")
      (node (ref "R9") (pin "2") (pinfunction "2_2") (pintype "passive"))
      (node (ref "U3") (pin "60") (pinfunction "BOOT0_60") (pintype "passive"))
    )
    (net (code "69") (name "Net-(U3-PB2{slash}BOOT1)") (class "Default")
      (node (ref "R14") (pin "2") (pinfunction "2_2") (pintype "passive"))
      (node (ref "U3") (pin "28") (pinfunction "PB2/BOOT1_28") (pintype "passive"))
    )
    (net (code "70") (name "Net-(U3-VDD_1)") (class "Default")
      (node (ref "R16") (pin "2") (pinfunction "2_2") (pintype "passive"))
      (node (ref "U3") (pin "32") (pinfunction "VDD_1_32") (pintype "passive"))
    )
    (net (code "71") (name "Net-(U3-VDD_2)") (class "Default")
      (node (ref "R11") (pin "1") (pinfunction "1_1") (pintype "passive"))
      (node (ref "U3") (pin "48") (pinfunction "VDD_2_48") (pintype "passive"))
    )
    (net (code "72") (name "Net-(U3-VDD_3)") (class "Default")
      (node (ref "R8") (pin "1") (pinfunction "1_1") (pintype "passive"))
      (node (ref "U3") (pin "64") (pinfunction "VDD_3_64") (pintype "passive"))
    )
    (net (code "73") (name "Net-(U3-VDD_4)") (class "Default")
      (node (ref "R13") (pin "2") (pinfunction "2_2") (pintype "passive"))
      (node (ref "U3") (pin "19") (pinfunction "VDD_4_19") (pintype "passive"))
    )
    (net (code "74") (name "Net-(U5-V3)") (class "Default")
      (node (ref "C13") (pin "1") (pinfunction "1_1") (pintype "passive"))
      (node (ref "U5") (pin "4") (pinfunction "V3_4") (pintype "passive"))
    )
    (net (code "75") (name "Net-(U5-XI)") (class "Default")
      (node (ref "C22") (pin "2") (pinfunction "2_2") (pintype "passive"))
      (node (ref "U5") (pin "7") (pinfunction "XI_7") (pintype "passive"))
      (node (ref "Y1") (pin "2") (pinfunction "OSC2_2") (pintype "passive"))
    )
    (net (code "76") (name "Net-(U5-XO)") (class "Default")
      (node (ref "C21") (pin "2") (pinfunction "2_2") (pintype "passive"))
      (node (ref "U5") (pin "8") (pinfunction "XO_8") (pintype "passive"))
      (node (ref "Y1") (pin "1") (pinfunction "OSC1_1") (pintype "passive"))
    )
    (net (code "77") (name "Net-(USB_SLAVE1-VCC)") (class "Default")
      (node (ref "F3") (pin "1") (pinfunction "1_1") (pintype "passive"))
      (node (ref "USB_SLAVE1") (pin "1") (pinfunction "VCC_1") (pintype "passive"))
    )
    (net (code "78") (name "VCC5") (class "Default")
      (node (ref "C11") (pin "1") (pinfunction "1_1") (pintype "passive"))
      (node (ref "C12") (pin "2") (pinfunction "2_2") (pintype "passive"))
      (node (ref "F2") (pin "2") (pinfunction "2_2") (pintype "passive"))
      (node (ref "F3") (pin "2") (pinfunction "2_2") (pintype "passive"))
      (node (ref "LED1") (pin "1") (pinfunction "A_1") (pintype "passive"))
      (node (ref "P11") (pin "1") (pinfunction "1_1") (pintype "passive"))
      (node (ref "P12") (pin "2") (pinfunction "2_2") (pintype "passive"))
      (node (ref "P12") (pin "6") (pinfunction "6_6") (pintype "passive"))
      (node (ref "P6") (pin "1") (pinfunction "1_1") (pintype "passive"))
      (node (ref "R15") (pin "2") (pinfunction "2_2") (pintype "passive"))
      (node (ref "R17") (pin "1") (pinfunction "1_1") (pintype "passive"))
      (node (ref "U4") (pin "3") (pinfunction "IN_3") (pintype "passive"))
      (node (ref "U5") (pin "16") (pinfunction "VCC_16") (pintype "passive"))
    )
    (net (code "79") (name "VCC24") (class "Default")
      (node (ref "C*1") (pin "1") (pinfunction "1_1") (pintype "passive"))
      (node (ref "C10") (pin "1") (pinfunction "1_1") (pintype "passive"))
      (node (ref "Ce2") (pin "1") (pinfunction "+_1") (pintype "passive"))
      (node (ref "J1") (pin "1") (pinfunction "1_1") (pintype "passive"))
      (node (ref "LED2") (pin "1") (pinfunction "A_1") (pintype "passive"))
      (node (ref "P12") (pin "1") (pinfunction "1_1") (pintype "passive"))
      (node (ref "P12") (pin "5") (pinfunction "5_5") (pintype "passive"))
      (node (ref "P6") (pin "3") (pinfunction "3_3") (pintype "passive"))
    )
    (net (code "80") (name "VDD") (class "Default")
      (node (ref "C14") (pin "2") (pinfunction "2_2") (pintype "passive"))
      (node (ref "C17") (pin "1") (pinfunction "1_1") (pintype "passive"))
      (node (ref "C18") (pin "1") (pinfunction "1_1") (pintype "passive"))
      (node (ref "C19") (pin "1") (pinfunction "1_1") (pintype "passive"))
      (node (ref "C20") (pin "2") (pinfunction "2_2") (pintype "passive"))
      (node (ref "D1") (pin "2") (pinfunction "K_2") (pintype "passive"))
      (node (ref "D2") (pin "2") (pinfunction "K_2") (pintype "passive"))
      (node (ref "F1") (pin "2") (pinfunction "2_2") (pintype "passive"))
      (node (ref "L1") (pin "1") (pinfunction "1_1") (pintype "passive"))
      (node (ref "P10") (pin "4") (pinfunction "4_4") (pintype "passive"))
      (node (ref "P12") (pin "3") (pinfunction "3_3") (pintype "passive"))
      (node (ref "P12") (pin "7") (pinfunction "7_7") (pintype "passive"))
      (node (ref "P7") (pin "3") (pinfunction "3_3") (pintype "passive"))
      (node (ref "R11") (pin "2") (pinfunction "2_2") (pintype "passive"))
      (node (ref "R13") (pin "1") (pinfunction "1_1") (pintype "passive"))
      (node (ref "R16") (pin "1") (pinfunction "1_1") (pintype "passive"))
      (node (ref "R19") (pin "1") (pinfunction "1_1") (pintype "passive"))
      (node (ref "R20") (pin "1") (pinfunction "1_1") (pintype "passive"))
      (node (ref "R21") (pin "1") (pinfunction "1_1") (pintype "passive"))
      (node (ref "R22") (pin "2") (pinfunction "2_2") (pintype "passive"))
      (node (ref "R8") (pin "2") (pinfunction "2_2") (pintype "passive"))
      (node (ref "U3") (pin "1") (pinfunction "VBAT_1") (pintype "passive"))
    )
    (net (code "81") (name "unconnected-(U5-CTS#-Pad9)") (class "Default")
      (node (ref "U5") (pin "9") (pinfunction "CTS#_9") (pintype "passive+no_connect"))
    )
    (net (code "82") (name "unconnected-(U5-DCD#-Pad12)") (class "Default")
      (node (ref "U5") (pin "12") (pinfunction "DCD#_12") (pintype "passive+no_connect"))
    )
    (net (code "83") (name "unconnected-(U5-DSR#-Pad10)") (class "Default")
      (node (ref "U5") (pin "10") (pinfunction "DSR#_10") (pintype "passive+no_connect"))
    )
    (net (code "84") (name "unconnected-(U5-DTR#-Pad13)") (class "Default")
      (node (ref "U5") (pin "13") (pinfunction "DTR#_13") (pintype "passive+no_connect"))
    )
    (net (code "85") (name "unconnected-(U5-R232-Pad15)") (class "Default")
      (node (ref "U5") (pin "15") (pinfunction "R232_15") (pintype "passive+no_connect"))
    )
    (net (code "86") (name "unconnected-(U5-RI#-Pad11)") (class "Default")
      (node (ref "U5") (pin "11") (pinfunction "RI#_11") (pintype "passive+no_connect"))
    )
    (net (code "87") (name "unconnected-(U5-RTS#-Pad14)") (class "Default")
      (node (ref "U5") (pin "14") (pinfunction "RTS#_14") (pintype "passive+no_connect"))
    )
    (net (code "88") (name "unconnected-(USB_SLAVE1-NC-Pad4)") (class "Default")
      (node (ref "USB_SLAVE1") (pin "4") (pinfunction "NC_4") (pintype "passive+no_connect"))
    )
  )
)
